# walktimizer_v1.net
KiCad netlist of a schematic drawn in Altium Designer
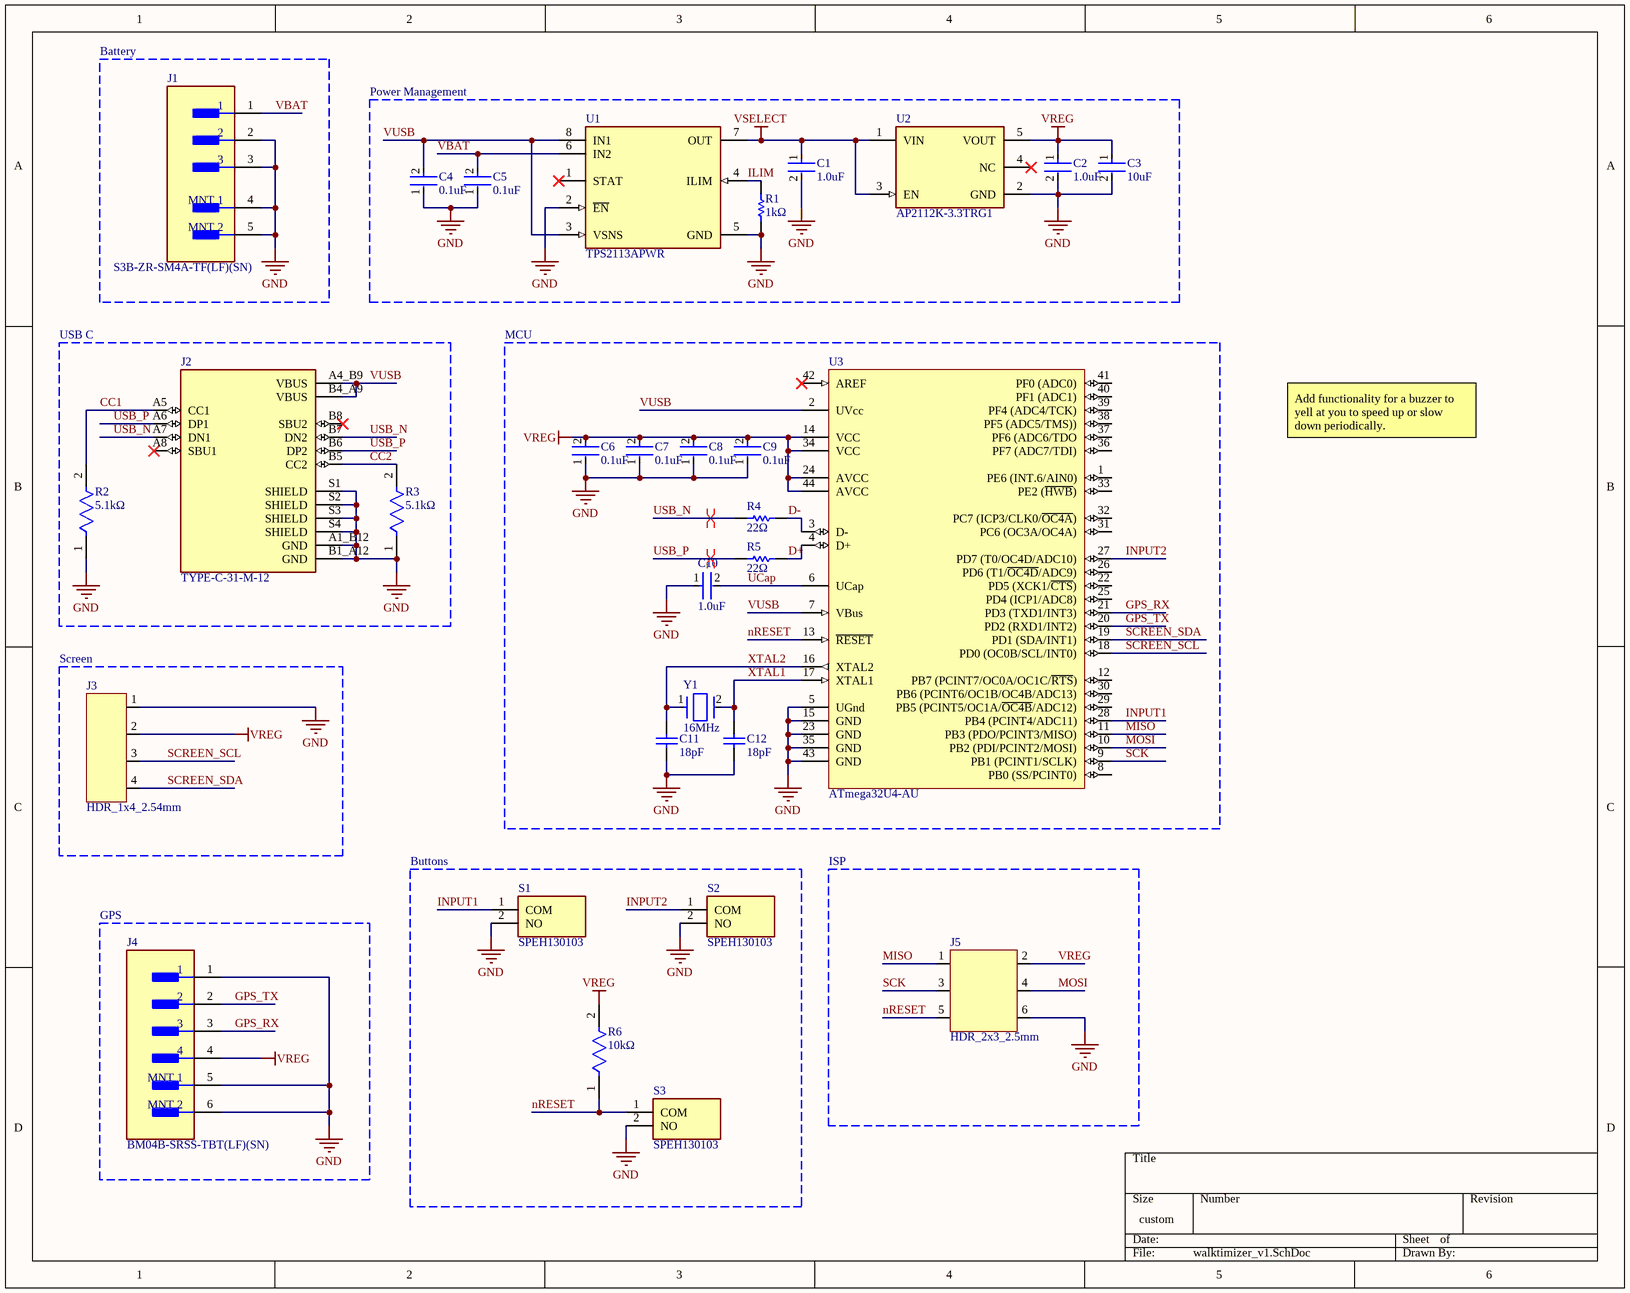
[diagram p0: walktimizer_v1.SchDoc]

(export (version "E")
  (design (tool "Eeschema 10.0.6"))
  (components
    (comp (ref "C1")
      (value "1.0uF")
      (footprint "FP-GRT188-0_1-e0_2_0_5-IPC_B")
      (description "Multi-Layer Ceramic Capacitor 1uF 50V X5R ±10% 0603 Paper T/R\r\nGRT188R61H105KE13D")
      (fields (field (name "TOLERANCE") "10%"))
      (libsource (lib "Altium Content Vault") (part "02cd4be3c70576c341d710602a673aa"))
    )
    (comp (ref "C2")
      (value "1.0uF")
      (footprint "FP-GRT188-0_1-e0_2_0_5-IPC_B")
      (description "Multi-Layer Ceramic Capacitor 1uF 50V X5R ±10% 0603 Paper T/R\r\nGRT188R61H105KE13D")
      (fields (field (name "TOLERANCE") "10%"))
      (libsource (lib "Altium Content Vault") (part "02cd4be3c70576c341d710602a673aa"))
    )
    (comp (ref "C3")
      (value "10uF")
      (footprint "FP-GRM188-0_1-e0_2_0_55-IPC_A")
      (fields (field (name "VOLTAGE") "6.3V") (field (name "TOLERANCE") "20%"))
      (libsource (lib "Altium Content Vault") (part "02cd4be3c70576c341d710602a673aa"))
    )
    (comp (ref "C4")
      (value "0.1uF")
      (footprint "FP-GRM15-MFG")
      (description "CAP CER 0.1UF 16V X7R 0402\r\n\r\nGRM155R71C104KA88D")
      (fields (field (name "MANUFACTURER PART NUMBER") "GRM155R71C104KA88D") (field (name "TOLERANCE") "10%"))
      (libsource (lib "Altium Content Vault") (part "236180d848d6139a670b325ea6854c9"))
    )
    (comp (ref "C5")
      (value "0.1uF")
      (footprint "FP-GRM15-MFG")
      (description "CAP CER 0.1UF 16V X7R 0402\r\n\r\nGRM155R71C104KA88D")
      (fields (field (name "MANUFACTURER PART NUMBER") "GRM155R71C104KA88D") (field (name "TOLERANCE") "10%"))
      (libsource (lib "Altium Content Vault") (part "236180d848d6139a670b325ea6854c9"))
    )
    (comp (ref "C6")
      (value "0.1uF")
      (footprint "FP-GRM15-MFG")
      (description "CAP CER 0.1UF 16V X7R 0402\r\n\r\nGRM155R71C104KA88D")
      (fields (field (name "MANUFACTURER PART NUMBER") "GRM155R71C104KA88D") (field (name "TOLERANCE") "10%"))
      (libsource (lib "Altium Content Vault") (part "236180d848d6139a670b325ea6854c9"))
    )
    (comp (ref "C7")
      (value "0.1uF")
      (footprint "FP-GRM15-MFG")
      (description "CAP CER 0.1UF 16V X7R 0402\r\n\r\nGRM155R71C104KA88D")
      (fields (field (name "MANUFACTURER PART NUMBER") "GRM155R71C104KA88D") (field (name "TOLERANCE") "10%"))
      (libsource (lib "Altium Content Vault") (part "236180d848d6139a670b325ea6854c9"))
    )
    (comp (ref "C8")
      (value "0.1uF")
      (footprint "FP-GRM15-MFG")
      (description "CAP CER 0.1UF 16V X7R 0402\r\n\r\nGRM155R71C104KA88D")
      (fields (field (name "MANUFACTURER PART NUMBER") "GRM155R71C104KA88D") (field (name "TOLERANCE") "10%"))
      (libsource (lib "Altium Content Vault") (part "236180d848d6139a670b325ea6854c9"))
    )
    (comp (ref "C9")
      (value "0.1uF")
      (footprint "FP-GRM15-MFG")
      (description "CAP CER 0.1UF 16V X7R 0402\r\n\r\nGRM155R71C104KA88D")
      (fields (field (name "MANUFACTURER PART NUMBER") "GRM155R71C104KA88D") (field (name "TOLERANCE") "10%"))
      (libsource (lib "Altium Content Vault") (part "236180d848d6139a670b325ea6854c9"))
    )
    (comp (ref "C10")
      (value "1.0uF")
      (footprint "FP-GRT188-0_1-e0_2_0_5-IPC_B")
      (description "Multi-Layer Ceramic Capacitor 1uF 50V X5R ±10% 0603 Paper T/R\r\nGRT188R61H105KE13D")
      (fields (field (name "TOLERANCE") "10%"))
      (libsource (lib "Altium Content Vault") (part "02cd4be3c70576c341d710602a673aa"))
    )
    (comp (ref "C11")
      (value "18pF")
      (footprint "CAPC1608X90X40LL10T20")
      (fields (field (name "TOLERANCE") "1%"))
      (libsource (lib "Altium Content Vault") (part "CAP-NP-2"))
    )
    (comp (ref "C12")
      (value "18pF")
      (footprint "CAPC1608X90X40LL10T20")
      (fields (field (name "TOLERANCE") "1%"))
      (libsource (lib "Altium Content Vault") (part "CAP-NP-2"))
    )
    (comp (ref "J1")
      (value "S3B-ZR-SM4A-TF(LF)(SN)")
      (footprint "FP-S3B-ZR-SM4A-TF_LF_SN-MFG")
      (description "CONN HEADER SMD R/A 3POS 1.5MM")
      (libsource (lib "Altium Content Vault") (part "38689d6f3df0f9b234c6ddcef280d85"))
    )
    (comp (ref "J2")
      (value "TYPE-C-31-M-12")
      (footprint "HRO_TYPE-C-31-M-12")
      (description "USB Connectors 24 Receptacle 1 8.94*7.3mm RoHS")
      (fields (field (name "MF") "HRO Electronics Co., Ltd."))
      (libsource (lib "TYPE-C-31-M-12") (part "TYPE-C-31-M-12"))
    )
    (comp (ref "J3")
      (value "HDR_1x4_2.54mm")
      (footprint "HDR_1x4_2.5mm_TH")
      (description "2x3 2.54mm Pitch Header")
      (libsource (lib "symbolism") (part "HDR_1x4_2.54mm"))
    )
    (comp (ref "J4")
      (value "BM04B-SRSS-TBT(LF)(SN)")
      (footprint "FP-BM04B-SRSS-TBT_LF_SN-MFG")
      (description "CONN HEADER SMD 4POS 1MM")
      (libsource (lib "Altium Content Vault") (part "8e3688c4b118bffc0dd9b7401e414ba"))
    )
    (comp (ref "J5")
      (value "HDR_2x3_2.5mm")
      (footprint "HDR_2x3_2.5mm_TH")
      (description "2x3 2.54mm Pitch Header")
      (libsource (lib "symbolism") (part "HDR_2x3_2.5mm"))
    )
    (comp (ref "R1")
      (value "1kΩ")
      (footprint "RESC2013X60X35ML10T20")
      (fields (field (name "TOLERANCE") "1%") (field (name "MANUFACTURER") "Yageo"))
      (libsource (lib "Altium Content Vault") (part "RES-2"))
    )
    (comp (ref "R2")
      (value "5.1kΩ")
      (footprint "FP-CRCW0603-e3-IPC_C")
      (description "RES Thick Film, 5.1kΩ, 1%, 0.1W, 100ppm/°C, 0603\r\n\r\nCRCW06035K10FKEA")
      (fields (field (name "TOLERANCE") "1%"))
      (libsource (lib "Altium Content Vault") (part "1029c3af85768c4190bb7ad29bc67b5"))
    )
    (comp (ref "R3")
      (value "5.1kΩ")
      (footprint "FP-CRCW0603-e3-IPC_C")
      (description "RES Thick Film, 5.1kΩ, 1%, 0.1W, 100ppm/°C, 0603\r\n\r\nCRCW06035K10FKEA")
      (fields (field (name "TOLERANCE") "1%"))
      (libsource (lib "Altium Content Vault") (part "1029c3af85768c4190bb7ad29bc67b5"))
    )
    (comp (ref "R4")
      (value "22Ω")
      (footprint "RESC1005X40X25LL05T05")
      (description "CRCW040222R0FKED")
      (fields (field (name "MANUFACTURER") "Vishay Dale"))
      (libsource (lib "Altium Content Vault") (part "RES"))
    )
    (comp (ref "R5")
      (value "22Ω")
      (footprint "RESC1005X40X25LL05T05")
      (description "CRCW040222R0FKED")
      (fields (field (name "MANUFACTURER") "Vishay Dale"))
      (libsource (lib "Altium Content Vault") (part "RES"))
    )
    (comp (ref "R6")
      (value "10kΩ")
      (footprint "FP-RC0603-0_55-IPC_C")
      (description "RES 10K OHM 1% 1/10W 0603\r\nRC0603FR-0710KL")
      (fields (field (name "TOLERANCE") "1%"))
      (libsource (lib "Altium Content Vault") (part "1029c3af85768c4190bb7ad29bc67b5"))
    )
    (comp (ref "S1")
      (value "SPEH130103")
      (footprint "SamacSys:SPEH130103")
      (description "Switch")
      (fields (field (name "MOUSER PART NUMBER") "688-SPEH130101"))
      (libsource (lib "*") (part "SPEH130103"))
    )
    (comp (ref "S2")
      (value "SPEH130103")
      (footprint "SamacSys:SPEH130103")
      (description "Switch")
      (fields (field (name "MOUSER PART NUMBER") "688-SPEH130101"))
      (libsource (lib "*") (part "SPEH130103"))
    )
    (comp (ref "S3")
      (value "SPEH130103")
      (footprint "SamacSys:SPEH130103")
      (description "Switch")
      (fields (field (name "MOUSER PART NUMBER") "688-SPEH130101"))
      (libsource (lib "*") (part "SPEH130103"))
    )
    (comp (ref "U1")
      (value "TPS2113APWR")
      (footprint "FP-PW0008A-IPC_B")
      (description "IC OR CTRLR SRC SELECT 8TSSOP")
      (libsource (lib "Altium Content Vault") (part "883c2ec5d874d1801bc805f681b0625"))
    )
    (comp (ref "U2")
      (value "AP2112K-3.3TRG1")
      (footprint "FP-SOT25-IPC_A")
      (description "IC REG LINEAR 3.3V 600MA SOT25")
      (libsource (lib "Altium Content Vault") (part "c8ab751aee5229183125ab046a11caa"))
    )
    (comp (ref "U3")
      (value "ATmega32U4-AU")
      (footprint "44ML_M")
      (libsource (lib "Altium Content Vault") (part "MC-8B-ATM16U4-SQ44"))
    )
    (comp (ref "Y1")
      (value "16MHz")
      (footprint "FP-ABM3-MFG")
      (description "Crystal 16MHz ±20ppm 18pF SMD-2 5mm x 3.2mm\r\n\r\nABM3-16.000MHZ-D2Y-T")
      (fields (field (name "TOLERANCE") "20ppm"))
      (libsource (lib "Altium Content Vault") (part "c23a69dc6c9e2f18f2079038eb95dd1"))
    )
  )
  (nets
    (net (code "1") (name "/CC1") (class "Default")
      (node (ref "J2") (pin "A5") (pinfunction "CC1_A5") (pintype "bidirectional"))
      (node (ref "R2") (pin "2") (pinfunction "2_2") (pintype "passive"))
    )
    (net (code "2") (name "/CC2") (class "Default")
      (node (ref "J2") (pin "B5") (pinfunction "CC2_B5") (pintype "bidirectional"))
      (node (ref "R3") (pin "2") (pinfunction "2_2") (pintype "passive"))
    )
    (net (code "3") (name "/D+") (class "Default")
      (node (ref "R5") (pin "2") (pinfunction "2_2") (pintype "passive"))
      (node (ref "U3") (pin "4") (pinfunction "D+_4") (pintype "bidirectional"))
    )
    (net (code "4") (name "/D-") (class "Default")
      (node (ref "R4") (pin "2") (pinfunction "2_2") (pintype "passive"))
      (node (ref "U3") (pin "3") (pinfunction "D-_3") (pintype "bidirectional"))
    )
    (net (code "5") (name "/GPS_RX") (class "Default")
      (node (ref "J4") (pin "3") (pinfunction "3_3") (pintype "passive"))
      (node (ref "U3") (pin "21") (pinfunction "PD3_(TXD1/INT3)_21") (pintype "bidirectional"))
    )
    (net (code "6") (name "/GPS_TX") (class "Default")
      (node (ref "J4") (pin "2") (pinfunction "2_2") (pintype "passive"))
      (node (ref "U3") (pin "20") (pinfunction "PD2_(RXD1/INT2)_20") (pintype "bidirectional"))
    )
    (net (code "7") (name "/ILIM") (class "Default")
      (node (ref "R1") (pin "2") (pinfunction "2_2") (pintype "passive"))
      (node (ref "U1") (pin "4") (pinfunction "ILIM_4") (pintype "input"))
    )
    (net (code "8") (name "/INPUT1") (class "Default")
      (node (ref "S1") (pin "1") (pinfunction "COM_1") (pintype "passive"))
      (node (ref "U3") (pin "28") (pinfunction "PB4_(PCINT4/ADC11)_28") (pintype "bidirectional"))
    )
    (net (code "9") (name "/INPUT2") (class "Default")
      (node (ref "S2") (pin "1") (pinfunction "COM_1") (pintype "passive"))
      (node (ref "U3") (pin "27") (pinfunction "PD7_(T0/OC4D/ADC10)_27") (pintype "bidirectional"))
    )
    (net (code "10") (name "/MISO") (class "Default")
      (node (ref "J5") (pin "1") (pintype "passive"))
      (node (ref "U3") (pin "11") (pinfunction "PB3_(PDO/PCINT3/MISO)_11") (pintype "bidirectional"))
    )
    (net (code "11") (name "/MOSI") (class "Default")
      (node (ref "J5") (pin "4") (pintype "passive"))
      (node (ref "U3") (pin "10") (pinfunction "PB2_(PDI/PCINT2/MOSI)_10") (pintype "bidirectional"))
    )
    (net (code "12") (name "/SCK") (class "Default")
      (node (ref "J5") (pin "3") (pintype "passive"))
      (node (ref "U3") (pin "9") (pinfunction "PB1_(PCINT1/SCLK)_9") (pintype "bidirectional"))
    )
    (net (code "13") (name "/SCREEN_SCL") (class "Default")
      (node (ref "J3") (pin "3") (pintype "passive"))
      (node (ref "U3") (pin "18") (pinfunction "PD0_(OC0B/SCL/INT0)_18") (pintype "bidirectional"))
    )
    (net (code "14") (name "/SCREEN_SDA") (class "Default")
      (node (ref "J3") (pin "4") (pintype "passive"))
      (node (ref "U3") (pin "19") (pinfunction "PD1_(SDA/INT1)_19") (pintype "bidirectional"))
    )
    (net (code "15") (name "/UCap") (class "Default")
      (node (ref "C10") (pin "2") (pinfunction "2_2") (pintype "passive"))
      (node (ref "U3") (pin "6") (pinfunction "UCap_6") (pintype "passive"))
    )
    (net (code "16") (name "/USB_N") (class "Default")
      (node (ref "J2") (pin "A7") (pinfunction "DN1_A7") (pintype "bidirectional"))
      (node (ref "J2") (pin "B7") (pinfunction "DN2_B7") (pintype "bidirectional"))
      (node (ref "R4") (pin "1") (pinfunction "1_1") (pintype "passive"))
    )
    (net (code "17") (name "/USB_P") (class "Default")
      (node (ref "J2") (pin "A6") (pinfunction "DP1_A6") (pintype "bidirectional"))
      (node (ref "J2") (pin "B6") (pinfunction "DP2_B6") (pintype "bidirectional"))
      (node (ref "R5") (pin "1") (pinfunction "1_1") (pintype "passive"))
    )
    (net (code "18") (name "/VBAT") (class "Default")
      (node (ref "C5") (pin "2") (pinfunction "2_2") (pintype "passive"))
      (node (ref "J1") (pin "1") (pinfunction "1_1") (pintype "passive"))
      (node (ref "U1") (pin "6") (pinfunction "IN2_6") (pintype "power_in"))
    )
    (net (code "19") (name "/VUSB") (class "Default")
      (node (ref "C4") (pin "2") (pinfunction "2_2") (pintype "passive"))
      (node (ref "J2") (pin "A4_B9") (pinfunction "VBUS_A4_B9") (pintype "power_in"))
      (node (ref "J2") (pin "B4_A9") (pinfunction "VBUS_B4_A9") (pintype "power_in"))
      (node (ref "U1") (pin "3") (pinfunction "VSNS_3") (pintype "input"))
      (node (ref "U1") (pin "8") (pinfunction "IN1_8") (pintype "power_in"))
      (node (ref "U3") (pin "2") (pinfunction "UVcc_2") (pintype "power_in"))
      (node (ref "U3") (pin "7") (pinfunction "VBus_7") (pintype "input"))
    )
    (net (code "20") (name "/XTAL1") (class "Default")
      (node (ref "C12") (pin "2") (pinfunction "2_2") (pintype "passive"))
      (node (ref "U3") (pin "17") (pinfunction "XTAL1_17") (pintype "input"))
      (node (ref "Y1") (pin "2") (pinfunction "2_2") (pintype "passive"))
    )
    (net (code "21") (name "/XTAL2") (class "Default")
      (node (ref "C11") (pin "2") (pinfunction "2_2") (pintype "passive"))
      (node (ref "U3") (pin "16") (pinfunction "XTAL2_16") (pintype "output"))
      (node (ref "Y1") (pin "1") (pinfunction "1_1") (pintype "passive"))
    )
    (net (code "22") (name "/nRESET") (class "Default")
      (node (ref "J5") (pin "5") (pintype "passive"))
      (node (ref "R6") (pin "1") (pinfunction "1_1") (pintype "passive"))
      (node (ref "S3") (pin "1") (pinfunction "COM_1") (pintype "passive"))
      (node (ref "U3") (pin "13") (pinfunction "~{RESET}_13") (pintype "input"))
    )
    (net (code "23") (name "GND") (class "Default")
      (node (ref "C1") (pin "2") (pinfunction "2_2") (pintype "passive"))
      (node (ref "C10") (pin "1") (pinfunction "1_1") (pintype "passive"))
      (node (ref "C11") (pin "1") (pinfunction "1_1") (pintype "passive"))
      (node (ref "C12") (pin "1") (pinfunction "1_1") (pintype "passive"))
      (node (ref "C2") (pin "2") (pinfunction "2_2") (pintype "passive"))
      (node (ref "C3") (pin "2") (pinfunction "2_2") (pintype "passive"))
      (node (ref "C4") (pin "1") (pinfunction "1_1") (pintype "passive"))
      (node (ref "C5") (pin "1") (pinfunction "1_1") (pintype "passive"))
      (node (ref "C6") (pin "1") (pinfunction "1_1") (pintype "passive"))
      (node (ref "C7") (pin "1") (pinfunction "1_1") (pintype "passive"))
      (node (ref "C8") (pin "1") (pinfunction "1_1") (pintype "passive"))
      (node (ref "C9") (pin "1") (pinfunction "1_1") (pintype "passive"))
      (node (ref "J1") (pin "2") (pinfunction "2_2") (pintype "passive"))
      (node (ref "J1") (pin "3") (pinfunction "3_3") (pintype "passive"))
      (node (ref "J1") (pin "4") (pinfunction "MNT_1_4") (pintype "passive"))
      (node (ref "J1") (pin "5") (pinfunction "MNT_2_5") (pintype "passive"))
      (node (ref "J2") (pin "A1_B12") (pinfunction "GND_A1_B12") (pintype "power_in"))
      (node (ref "J2") (pin "B1_A12") (pinfunction "GND_B1_A12") (pintype "power_in"))
      (node (ref "J2") (pin "S1") (pinfunction "SHIELD_S1") (pintype "passive"))
      (node (ref "J2") (pin "S2") (pinfunction "SHIELD_S2") (pintype "passive"))
      (node (ref "J2") (pin "S3") (pinfunction "SHIELD_S3") (pintype "passive"))
      (node (ref "J2") (pin "S4") (pinfunction "SHIELD_S4") (pintype "passive"))
      (node (ref "J3") (pin "1") (pintype "passive"))
      (node (ref "J4") (pin "1") (pinfunction "1_1") (pintype "passive"))
      (node (ref "J4") (pin "5") (pinfunction "MNT_1_5") (pintype "passive"))
      (node (ref "J4") (pin "6") (pinfunction "MNT_2_6") (pintype "passive"))
      (node (ref "J5") (pin "6") (pintype "passive"))
      (node (ref "R1") (pin "1") (pinfunction "1_1") (pintype "passive"))
      (node (ref "R2") (pin "1") (pinfunction "1_1") (pintype "passive"))
      (node (ref "R3") (pin "1") (pinfunction "1_1") (pintype "passive"))
      (node (ref "S1") (pin "2") (pinfunction "NO_2") (pintype "passive"))
      (node (ref "S2") (pin "2") (pinfunction "NO_2") (pintype "passive"))
      (node (ref "S3") (pin "2") (pinfunction "NO_2") (pintype "passive"))
      (node (ref "U1") (pin "2") (pinfunction "~{EN}_2") (pintype "input"))
      (node (ref "U1") (pin "5") (pinfunction "GND_5") (pintype "power_in"))
      (node (ref "U2") (pin "2") (pinfunction "GND_2") (pintype "power_in"))
      (node (ref "U3") (pin "15") (pinfunction "GND_15") (pintype "power_in"))
      (node (ref "U3") (pin "23") (pinfunction "GND_23") (pintype "power_in"))
      (node (ref "U3") (pin "35") (pinfunction "GND_35") (pintype "power_in"))
      (node (ref "U3") (pin "43") (pinfunction "GND_43") (pintype "power_in"))
      (node (ref "U3") (pin "5") (pinfunction "UGnd_5") (pintype "power_in"))
    )
    (net (code "24") (name "VREG") (class "Default")
      (node (ref "C2") (pin "1") (pinfunction "1_1") (pintype "passive"))
      (node (ref "C3") (pin "1") (pinfunction "1_1") (pintype "passive"))
      (node (ref "C6") (pin "2") (pinfunction "2_2") (pintype "passive"))
      (node (ref "C7") (pin "2") (pinfunction "2_2") (pintype "passive"))
      (node (ref "C8") (pin "2") (pinfunction "2_2") (pintype "passive"))
      (node (ref "C9") (pin "2") (pinfunction "2_2") (pintype "passive"))
      (node (ref "J3") (pin "2") (pintype "passive"))
      (node (ref "J4") (pin "4") (pinfunction "4_4") (pintype "passive"))
      (node (ref "J5") (pin "2") (pintype "passive"))
      (node (ref "R6") (pin "2") (pinfunction "2_2") (pintype "passive"))
      (node (ref "U2") (pin "5") (pinfunction "VOUT_5") (pintype "power_in"))
      (node (ref "U3") (pin "14") (pinfunction "VCC_14") (pintype "power_in"))
      (node (ref "U3") (pin "24") (pinfunction "AVCC_24") (pintype "power_in"))
      (node (ref "U3") (pin "34") (pinfunction "VCC_34") (pintype "power_in"))
      (node (ref "U3") (pin "44") (pinfunction "AVCC_44") (pintype "power_in"))
    )
    (net (code "25") (name "VSELECT") (class "Default")
      (node (ref "C1") (pin "1") (pinfunction "1_1") (pintype "passive"))
      (node (ref "U1") (pin "7") (pinfunction "OUT_7") (pintype "power_in"))
      (node (ref "U2") (pin "1") (pinfunction "VIN_1") (pintype "power_in"))
      (node (ref "U2") (pin "3") (pinfunction "EN_3") (pintype "input"))
    )
    (net (code "26") (name "unconnected-(J2-SBU1-PadA8)") (class "Default")
      (node (ref "J2") (pin "A8") (pinfunction "SBU1_A8") (pintype "bidirectional+no_connect"))
    )
    (net (code "27") (name "unconnected-(J2-SBU2-PadB8)") (class "Default")
      (node (ref "J2") (pin "B8") (pinfunction "SBU2_B8") (pintype "bidirectional+no_connect"))
    )
    (net (code "28") (name "unconnected-(U1-STAT-Pad1)") (class "Default")
      (node (ref "U1") (pin "1") (pinfunction "STAT_1") (pintype "tri_state+no_connect"))
    )
    (net (code "29") (name "unconnected-(U2-NC-Pad4)") (class "Default")
      (node (ref "U2") (pin "4") (pinfunction "NC_4") (pintype "passive+no_connect"))
    )
    (net (code "30") (name "unconnected-(U3-AREF-Pad42)") (class "Default")
      (node (ref "U3") (pin "42") (pinfunction "AREF_42") (pintype "input+no_connect"))
    )
    (net (code "31") (name "unconnected-(U3-PB0_(SS{slash}PCINT0)-Pad8)") (class "Default")
      (node (ref "U3") (pin "8") (pinfunction "PB0_(SS/PCINT0)_8") (pintype "bidirectional"))
    )
    (net (code "32") (name "unconnected-(U3-PB5_(PCINT5{slash}OC1A{slash}~{OC4B}{slash}ADC12)-Pad29)") (class "Default")
      (node (ref "U3") (pin "29") (pinfunction "PB5_(PCINT5/OC1A/~{OC4B}/ADC12)_29") (pintype "bidirectional"))
    )
    (net (code "33") (name "unconnected-(U3-PB6_(PCINT6{slash}OC1B{slash}OC4B{slash}ADC13)-Pad30)") (class "Default")
      (node (ref "U3") (pin "30") (pinfunction "PB6_(PCINT6/OC1B/OC4B/ADC13)_30") (pintype "bidirectional"))
    )
    (net (code "34") (name "unconnected-(U3-PB7_(PCINT7{slash}OC0A{slash}OC1C{slash}~{RTS})-Pad12)") (class "Default")
      (node (ref "U3") (pin "12") (pinfunction "PB7_(PCINT7/OC0A/OC1C/~{RTS})_12") (pintype "bidirectional"))
    )
    (net (code "35") (name "unconnected-(U3-PC6_(OC3A{slash}OC4A)-Pad31)") (class "Default")
      (node (ref "U3") (pin "31") (pinfunction "PC6_(OC3A/OC4A)_31") (pintype "bidirectional"))
    )
    (net (code "36") (name "unconnected-(U3-PC7_(ICP3{slash}CLK0{slash}~{OC4A})-Pad32)") (class "Default")
      (node (ref "U3") (pin "32") (pinfunction "PC7_(ICP3/CLK0/~{OC4A})_32") (pintype "bidirectional"))
    )
    (net (code "37") (name "unconnected-(U3-PD4_(ICP1{slash}ADC8)-Pad25)") (class "Default")
      (node (ref "U3") (pin "25") (pinfunction "PD4_(ICP1/ADC8)_25") (pintype "bidirectional"))
    )
    (net (code "38") (name "unconnected-(U3-PD5_(XCK1{slash}~{CTS})-Pad22)") (class "Default")
      (node (ref "U3") (pin "22") (pinfunction "PD5_(XCK1/~{CTS})_22") (pintype "bidirectional"))
    )
    (net (code "39") (name "unconnected-(U3-PD6_(T1{slash}~{OC4D}{slash}ADC9)-Pad26)") (class "Default")
      (node (ref "U3") (pin "26") (pinfunction "PD6_(T1/~{OC4D}/ADC9)_26") (pintype "bidirectional"))
    )
    (net (code "40") (name "unconnected-(U3-PE2_(~{HWB})-Pad33)") (class "Default")
      (node (ref "U3") (pin "33") (pinfunction "PE2_(~{HWB})_33") (pintype "bidirectional"))
    )
    (net (code "41") (name "unconnected-(U3-PE6_(INT.6{slash}AIN0)-Pad1)") (class "Default")
      (node (ref "U3") (pin "1") (pinfunction "PE6_(INT.6/AIN0)_1") (pintype "bidirectional"))
    )
    (net (code "42") (name "unconnected-(U3-PF0_(ADC0)-Pad41)") (class "Default")
      (node (ref "U3") (pin "41") (pinfunction "PF0_(ADC0)_41") (pintype "bidirectional"))
    )
    (net (code "43") (name "unconnected-(U3-PF1_(ADC1)-Pad40)") (class "Default")
      (node (ref "U3") (pin "40") (pinfunction "PF1_(ADC1)_40") (pintype "bidirectional"))
    )
    (net (code "44") (name "unconnected-(U3-PF4_(ADC4{slash}TCK)-Pad39)") (class "Default")
      (node (ref "U3") (pin "39") (pinfunction "PF4_(ADC4/TCK)_39") (pintype "bidirectional"))
    )
    (net (code "45") (name "unconnected-(U3-PF5_(ADC5{slash}TMS))-Pad38)") (class "Default")
      (node (ref "U3") (pin "38") (pinfunction "PF5_(ADC5/TMS))_38") (pintype "bidirectional"))
    )
    (net (code "46") (name "unconnected-(U3-PF6_(ADC6{slash}TDO-Pad37)") (class "Default")
      (node (ref "U3") (pin "37") (pinfunction "PF6_(ADC6/TDO_37") (pintype "bidirectional"))
    )
    (net (code "47") (name "unconnected-(U3-PF7_(ADC7{slash}TDI)-Pad36)") (class "Default")
      (node (ref "U3") (pin "36") (pinfunction "PF7_(ADC7/TDI)_36") (pintype "bidirectional"))
    )
  )
)
